# 02_MCU.net
KiCad netlist of a schematic drawn in Altium Designer
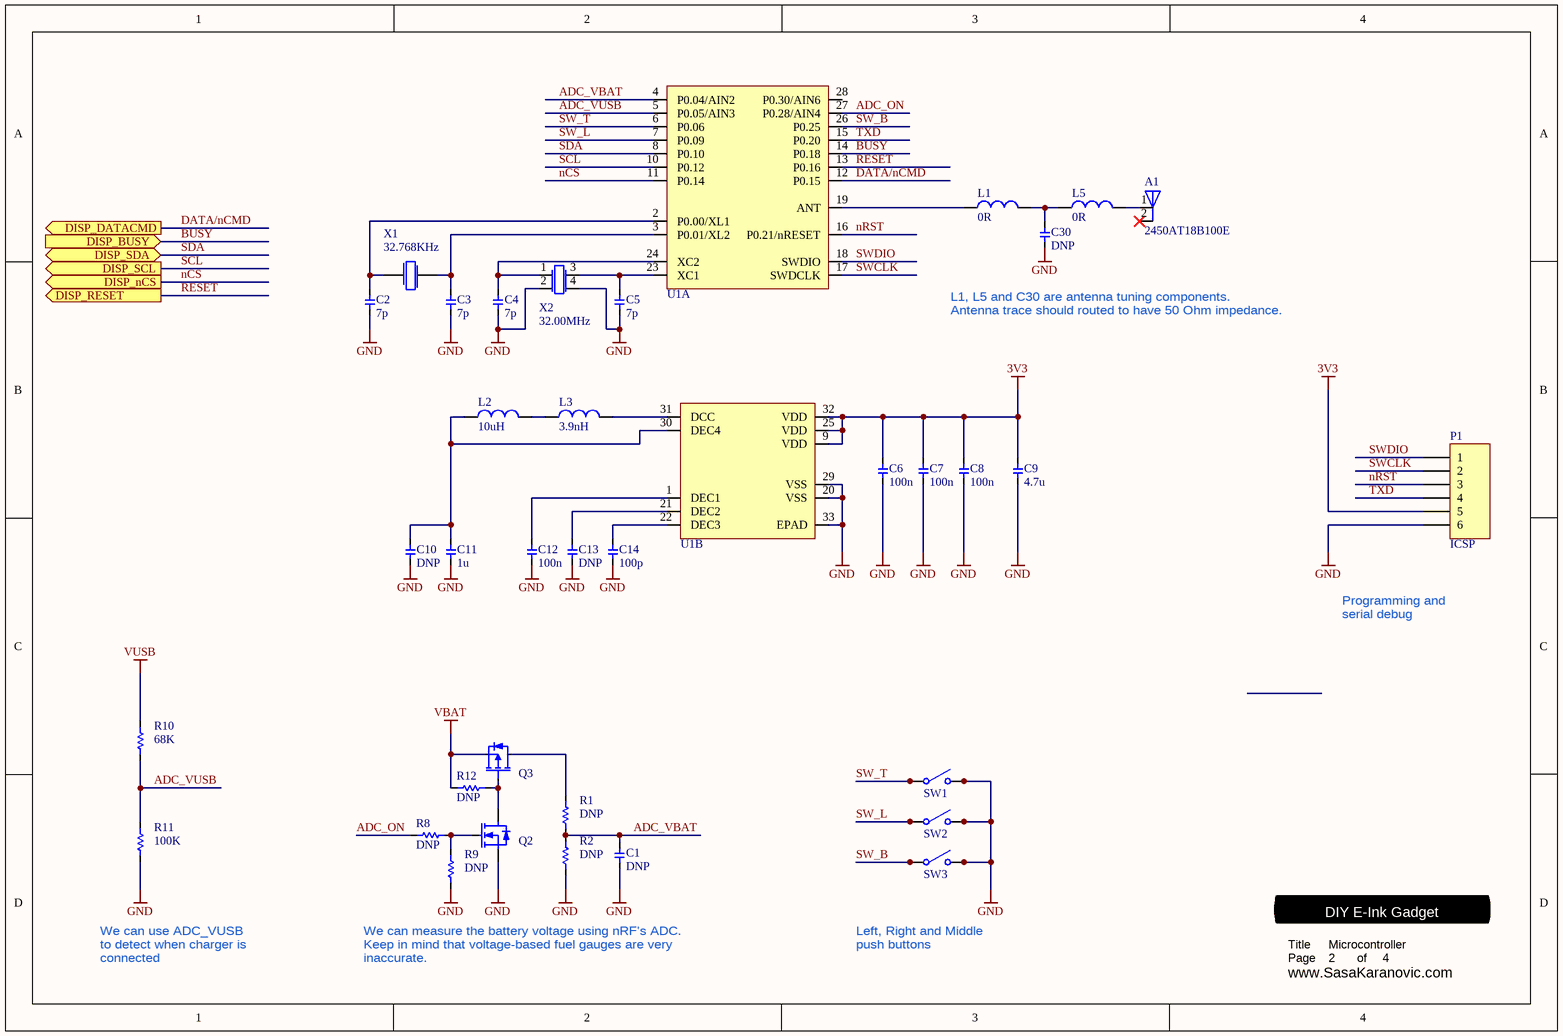
[diagram p0: 02_MCU.SchDoc]

(export (version "E")
  (design (tool "Eeschema 10.0.6"))
  (components
    (comp (ref "A1")
      (value "2450AT18B100E")
      (footprint "Footprint_Misc:2450AT18B100")
      (description "2.4GHz - Chip RF Antenna 2.4GHz ~ 2.5GHz 0.5dBi Solder Surface Mount")
      (fields
        (field (name "MANUFACTURER") "Johanson Technology Inc.")
        (field (name "DISTRIBUTOR PART NUMBER") "712-1006-1-ND")
      )
      (libsource (lib "Schematic_Misc") (part "2450AT18B100E"))
    )
    (comp (ref "C1")
      (value "DNP")
      (footprint "Footprint_Misc:0603 - CAP")
      (description "Capacitor")
      (fields (field (name "Comment") "Cap"))
      (libsource (lib "Schematic_Misc") (part "Cap"))
    )
    (comp (ref "C2")
      (value "7p")
      (footprint "Footprint_Misc:0603 - CAP")
      (description "Capacitor")
      (fields
        (field (name "MANUFACTURER") "Samsung Electro-Mechanics")
        (field (name "MANUFACTURER PART NUMBER") "CL10C070DB8NNNC")
      )
      (libsource (lib "Schematic_Misc") (part "Cap"))
    )
    (comp (ref "C3")
      (value "7p")
      (footprint "Footprint_Misc:0603 - CAP")
      (description "Capacitor")
      (fields
        (field (name "MANUFACTURER") "Samsung Electro-Mechanics")
        (field (name "MANUFACTURER PART NUMBER") "CL10C070DB8NNNC")
      )
      (libsource (lib "Schematic_Misc") (part "Cap"))
    )
    (comp (ref "C4")
      (value "7p")
      (footprint "Footprint_Misc:0603 - CAP")
      (description "Capacitor")
      (fields
        (field (name "MANUFACTURER") "Samsung Electro-Mechanics")
        (field (name "MANUFACTURER PART NUMBER") "CL10C070DB8NNNC")
      )
      (libsource (lib "Schematic_Misc") (part "Cap"))
    )
    (comp (ref "C5")
      (value "7p")
      (footprint "Footprint_Misc:0603 - CAP")
      (description "Capacitor")
      (fields
        (field (name "MANUFACTURER") "Samsung Electro-Mechanics")
        (field (name "MANUFACTURER PART NUMBER") "CL10C070DB8NNNC")
      )
      (libsource (lib "Schematic_Misc") (part "Cap"))
    )
    (comp (ref "C6")
      (value "100n")
      (footprint "Footprint_Misc:0603 - CAP")
      (description "Capacitor")
      (fields
        (field (name "MANUFACTURER") "Samsung Electro-Mechanics")
        (field (name "MANUFACTURER PART NUMBER") "CL10B104KB8NNWC")
      )
      (libsource (lib "Schematic_Misc") (part "Cap"))
    )
    (comp (ref "C7")
      (value "100n")
      (footprint "Footprint_Misc:0603 - CAP")
      (description "Capacitor")
      (fields
        (field (name "MANUFACTURER") "Samsung Electro-Mechanics")
        (field (name "MANUFACTURER PART NUMBER") "CL10B104KB8NNWC")
      )
      (libsource (lib "Schematic_Misc") (part "Cap"))
    )
    (comp (ref "C8")
      (value "100n")
      (footprint "Footprint_Misc:0603 - CAP")
      (description "Capacitor")
      (fields
        (field (name "MANUFACTURER") "Samsung Electro-Mechanics")
        (field (name "MANUFACTURER PART NUMBER") "CL10B104KB8NNWC")
      )
      (libsource (lib "Schematic_Misc") (part "Cap"))
    )
    (comp (ref "C9")
      (value "4.7u")
      (footprint "Footprint_Misc:0603 - CAP")
      (description "Capacitor")
      (fields
        (field (name "MANUFACTURER") "Samsung Electro-Mechanics")
        (field (name "MANUFACTURER PART NUMBER") "CL10B475KQ8NQNC")
      )
      (libsource (lib "Schematic_Misc") (part "Cap"))
    )
    (comp (ref "C10")
      (value "DNP")
      (footprint "Footprint_Misc:0603 - CAP")
      (description "Capacitor")
      (fields (field (name "Comment") "Cap"))
      (libsource (lib "Schematic_Misc") (part "Cap"))
    )
    (comp (ref "C11")
      (value "1u")
      (footprint "Footprint_Misc:0603 - CAP")
      (description "Capacitor")
      (fields
        (field (name "MANUFACTURER") "Samsung Electro-Mechanics")
        (field (name "MANUFACTURER PART NUMBER") "CL10B105KA8VPNC")
      )
      (libsource (lib "Schematic_Misc") (part "Cap"))
    )
    (comp (ref "C12")
      (value "100n")
      (footprint "Footprint_Misc:0603 - CAP")
      (description "Capacitor")
      (fields
        (field (name "MANUFACTURER") "Samsung Electro-Mechanics")
        (field (name "MANUFACTURER PART NUMBER") "CL10B104KB8NNWC")
      )
      (libsource (lib "Schematic_Misc") (part "Cap"))
    )
    (comp (ref "C13")
      (value "DNP")
      (footprint "Footprint_Misc:0603 - CAP")
      (description "Capacitor")
      (fields (field (name "Comment") "Cap"))
      (libsource (lib "Schematic_Misc") (part "Cap"))
    )
    (comp (ref "C14")
      (value "100p")
      (footprint "Footprint_Misc:0603 - CAP")
      (description "Capacitor")
      (fields
        (field (name "MANUFACTURER") "Samsung Electro-Mechanics")
        (field (name "MANUFACTURER PART NUMBER") "CL10C101JB8NNNC")
      )
      (libsource (lib "Schematic_Misc") (part "Cap"))
    )
    (comp (ref "C30")
      (value "DNP")
      (footprint "Footprint_Misc:0603 - CAP")
      (description "Capacitor")
      (fields (field (name "Comment") "Cap"))
      (libsource (lib "Schematic_Misc") (part "Cap"))
    )
    (comp (ref "L1")
      (value "0R")
      (footprint "Footprint_Misc:0603_IND")
      (description "Inductor")
      (fields
        (field (name "MANUFACTURER") "YAGEO")
        (field (name "MANUFACTURER PART NUMBER") "RC0603FR-070RL")
      )
      (libsource (lib "Schematic_Misc") (part "Inductor"))
    )
    (comp (ref "L2")
      (value "10uH")
      (footprint "Footprint_Misc:0603_IND")
      (description "Inductor")
      (fields
        (field (name "MANUFACTURER") "Abracon LLC")
        (field (name "MANUFACTURER PART NUMBER") "ASMCI-0603-100M-T")
      )
      (libsource (lib "Schematic_Misc") (part "Inductor"))
    )
    (comp (ref "L3")
      (value "3.9nH")
      (footprint "Footprint_Misc:0603_IND")
      (description "Inductor")
      (fields
        (field (name "MANUFACTURER") "Abracon LLC")
        (field (name "MANUFACTURER PART NUMBER") "AIMC-0603-3N9S-T")
      )
      (libsource (lib "Schematic_Misc") (part "Inductor"))
    )
    (comp (ref "L5")
      (value "0R")
      (footprint "Footprint_Misc:0603_IND")
      (description "Inductor")
      (fields
        (field (name "MANUFACTURER") "YAGEO")
        (field (name "MANUFACTURER PART NUMBER") "RC0603FR-070RL")
      )
      (libsource (lib "Schematic_Misc") (part "Inductor"))
    )
    (comp (ref "P1")
      (value "ICSP")
      (footprint "Footprint_Misc:Header 6x1 M - 90Deg - SMT")
      (description "Header, 6-Pin")
      (libsource (lib "Schematic_Misc") (part "Header 6"))
    )
    (comp (ref "Q2")
      (value "DMN62D0U-13")
      (footprint "Moji Footprintovi:SOT90P240X100-3N")
      (description "MOSFET N-CH 60V 0.38A")
      (fields
        (field (name "MANUFACTURER") "Diodes Incorporated")
        (field (name "DISTRIBUTOR PART NUMBER") "DMN62D0U-13DICT-ND")
      )
      (libsource (lib "Moji Schematici (1)") (part "DMN62D0U-13"))
    )
    (comp (ref "Q3")
      (value "DMP3017SFG")
      (footprint "Footprint_Misc:SOT-23")
      (description "P-Channel MOSFET")
      (libsource (lib "Schematic_Misc") (part "DMP3017SFG"))
    )
    (comp (ref "R1")
      (value "DNP")
      (footprint "Footprint_Misc:0603")
      (description "Resistor")
      (fields (field (name "Comment") "Res"))
      (libsource (lib "Schematic_Misc") (part "Res"))
    )
    (comp (ref "R2")
      (value "DNP")
      (footprint "Footprint_Misc:0603")
      (description "Resistor")
      (fields (field (name "Comment") "Res"))
      (libsource (lib "Schematic_Misc") (part "Res"))
    )
    (comp (ref "R8")
      (value "DNP")
      (footprint "Footprint_Misc:0603")
      (description "Resistor")
      (fields (field (name "Comment") "Res"))
      (libsource (lib "Schematic_Misc") (part "Res"))
    )
    (comp (ref "R9")
      (value "DNP")
      (footprint "Footprint_Misc:0603")
      (description "Resistor")
      (fields (field (name "Comment") "Res"))
      (libsource (lib "Schematic_Misc") (part "Res"))
    )
    (comp (ref "R10")
      (value "68K")
      (footprint "Footprint_Misc:0603")
      (description "Resistor")
      (fields
        (field (name "DISTRIBUTOR PART NUMBER") "311-68.0KHRCT-ND")
        (field (name "MANUFACTURER") "YAGEO")
      )
      (libsource (lib "Schematic_Misc") (part "Res"))
    )
    (comp (ref "R11")
      (value "100K")
      (footprint "Footprint_Misc:0603")
      (description "Resistor")
      (fields
        (field (name "DISTRIBUTOR PART NUMBER") "311-100KHRCT-ND")
        (field (name "MANUFACTURER") "YAGEO")
      )
      (libsource (lib "Schematic_Misc") (part "Res"))
    )
    (comp (ref "R12")
      (value "DNP")
      (footprint "Footprint_Misc:0603")
      (description "Resistor")
      (fields (field (name "Comment") "Res"))
      (libsource (lib "Schematic_Misc") (part "Res"))
    )
    (comp (ref "SW1")
      (value "SWITCH TACTILE SPST-NO 0.05A 12V")
      (footprint "Moji Footprintovi:PTS645")
      (fields
        (field (name "DISTRIBUTOR PART NUMBER") "CKN9088CT-ND")
        (field (name "MANUFACTURER") "C&K")
        (field (name "MANUFACTURER PART NUMBER") "PTS645SL50SMTR92 LFS")
      )
      (libsource (lib "Schematic_Misc") (part "PTS645SL50SMTR92 LFS"))
    )
    (comp (ref "SW2")
      (value "SWITCH TACTILE SPST-NO 0.05A 12V")
      (footprint "Moji Footprintovi:PTS645")
      (fields
        (field (name "DISTRIBUTOR PART NUMBER") "CKN9088CT-ND")
        (field (name "MANUFACTURER") "C&K")
        (field (name "MANUFACTURER PART NUMBER") "PTS645SL50SMTR92 LFS")
      )
      (libsource (lib "Schematic_Misc") (part "PTS645SL50SMTR92 LFS"))
    )
    (comp (ref "SW3")
      (value "SWITCH TACTILE SPST-NO 0.05A 12V")
      (footprint "Moji Footprintovi:PTS645")
      (fields
        (field (name "DISTRIBUTOR PART NUMBER") "CKN9088CT-ND")
        (field (name "MANUFACTURER") "C&K")
        (field (name "MANUFACTURER PART NUMBER") "PTS645SL50SMTR92 LFS")
      )
      (libsource (lib "Schematic_Misc") (part "PTS645SL50SMTR92 LFS"))
    )
    (comp (ref "U1")
      (value "NRF52810-QCAA-R")
      (footprint "Footprint_Misc:QFN50P500X500X100_HS-33N")
      (description "IC RF TxRx + MCU Bluetooth Bluetooth v5.0 2.4GHz 32-VFQFN Exposed Pad")
      (fields
        (field (name "MANUFACTURER") "Nordic Semiconductor ASA")
        (field (name "DISTRIBUTOR PART NUMBER") "1490-NRF52810-QCAA-RCT-ND")
      )
      (libsource (lib "Schematic_Misc") (part "NRF52810-QCAA-R"))
    )
    (comp (ref "X1")
      (value "32.768KHz")
      (footprint "Footprint_Misc:XTAL-2LEAD-3215")
      (description "32.768 kHz ±20ppm Crystal 7pF 70 kOhms 2-SMD, No Lead")
      (fields
        (field (name "MANUFACTURER") "ECS Inc.")
        (field (name "MANUFACTURER PART NUMBER") "ECS-320-8-37B-CKY-TR")
      )
      (libsource (lib "Schematic_Misc") (part "XTAL-32.768KHz-SC32S-7PF20PPM"))
    )
    (comp (ref "X2")
      (value "32.00MHz")
      (footprint "Footprint_Misc:XTAL-4LEAD-2016")
      (description "32 MHz ±10ppm Crystal 8pF 50 Ohms 4-SMD, No Lead")
      (fields
        (field (name "MANUFACTURER") "ECS Inc.")
        (field (name "MANUFACTURER PART NUMBER") "ECS-320-8-37B-CKY-TR")
      )
      (libsource (lib "Schematic_Misc") (part "XTAL-32MHz-ECS-320-8-37B-CKY-TR"))
    )
  )
  (nets
    (net (code "1") (name "/ADC_ON") (class "Default")
      (node (ref "R8") (pin "2") (pinfunction "2_2") (pintype "passive"))
      (node (ref "U1") (pin "27") (pinfunction "_P0.28/AIN4_27") (pintype "passive"))
    )
    (net (code "2") (name "/ADC_VBAT") (class "Default")
      (node (ref "C1") (pin "2") (pinfunction "2_2") (pintype "passive"))
      (node (ref "R1") (pin "1") (pinfunction "1_1") (pintype "passive"))
      (node (ref "R2") (pin "2") (pinfunction "2_2") (pintype "passive"))
      (node (ref "U1") (pin "4") (pinfunction "_P0.04/AIN2_4") (pintype "passive"))
    )
    (net (code "3") (name "/ADC_VUSB") (class "Default")
      (node (ref "R10") (pin "1") (pinfunction "1_1") (pintype "passive"))
      (node (ref "R11") (pin "2") (pinfunction "2_2") (pintype "passive"))
      (node (ref "U1") (pin "5") (pinfunction "_P0.05/AIN3_5") (pintype "passive"))
    )
    (net (code "4") (name "/BUSY") (class "Default")
      (node (ref "U1") (pin "14") (pinfunction "_P0.18_14") (pintype "passive"))
    )
    (net (code "5") (name "/DATA{slash}nCMD") (class "Default")
      (node (ref "U1") (pin "12") (pinfunction "_P0.15_12") (pintype "passive"))
    )
    (net (code "6") (name "/RESET") (class "Default")
      (node (ref "U1") (pin "13") (pinfunction "_P0.16_13") (pintype "passive"))
    )
    (net (code "7") (name "/SCL") (class "Default")
      (node (ref "U1") (pin "10") (pinfunction "_P0.12_10") (pintype "passive"))
    )
    (net (code "8") (name "/SDA") (class "Default")
      (node (ref "U1") (pin "8") (pinfunction "_P0.10_8") (pintype "passive"))
    )
    (net (code "9") (name "/SWCLK") (class "Default")
      (node (ref "P1") (pin "2") (pinfunction "2_2") (pintype "passive"))
      (node (ref "U1") (pin "17") (pinfunction "_SWDCLK_17") (pintype "passive"))
    )
    (net (code "10") (name "/SWDIO") (class "Default")
      (node (ref "P1") (pin "1") (pinfunction "1_1") (pintype "passive"))
      (node (ref "U1") (pin "18") (pinfunction "_SWDIO_18") (pintype "passive"))
    )
    (net (code "11") (name "/SW_B") (class "Default")
      (node (ref "SW3") (pin "1") (pinfunction "COMMON1_1") (pintype "passive"))
      (node (ref "SW3") (pin "2") (pinfunction "COMMON1_2") (pintype "passive"))
      (node (ref "U1") (pin "26") (pinfunction "_P0.25_26") (pintype "passive"))
    )
    (net (code "12") (name "/SW_L") (class "Default")
      (node (ref "SW2") (pin "1") (pinfunction "COMMON1_1") (pintype "passive"))
      (node (ref "SW2") (pin "2") (pinfunction "COMMON1_2") (pintype "passive"))
      (node (ref "U1") (pin "7") (pinfunction "_P0.09_7") (pintype "passive"))
    )
    (net (code "13") (name "/SW_T") (class "Default")
      (node (ref "SW1") (pin "1") (pinfunction "COMMON1_1") (pintype "passive"))
      (node (ref "SW1") (pin "2") (pinfunction "COMMON1_2") (pintype "passive"))
      (node (ref "U1") (pin "6") (pinfunction "_P0.06_6") (pintype "passive"))
    )
    (net (code "14") (name "/TXD") (class "Default")
      (node (ref "P1") (pin "4") (pinfunction "4_4") (pintype "passive"))
      (node (ref "U1") (pin "15") (pinfunction "_P0.20_15") (pintype "passive"))
    )
    (net (code "15") (name "/nCS") (class "Default")
      (node (ref "U1") (pin "11") (pinfunction "_P0.14_11") (pintype "passive"))
    )
    (net (code "16") (name "/nRST") (class "Default")
      (node (ref "P1") (pin "3") (pinfunction "3_3") (pintype "passive"))
      (node (ref "U1") (pin "16") (pinfunction "_P0.21/nRESET_16") (pintype "passive"))
    )
    (net (code "17") (name "3V3") (class "Default")
      (node (ref "C6") (pin "2") (pinfunction "2_2") (pintype "passive"))
      (node (ref "C7") (pin "2") (pinfunction "2_2") (pintype "passive"))
      (node (ref "C8") (pin "2") (pinfunction "2_2") (pintype "passive"))
      (node (ref "C9") (pin "2") (pinfunction "2_2") (pintype "passive"))
      (node (ref "P1") (pin "5") (pinfunction "5_5") (pintype "passive"))
      (node (ref "U1") (pin "25") (pinfunction "_VDD_25") (pintype "passive"))
      (node (ref "U1") (pin "32") (pinfunction "_VDD_32") (pintype "passive"))
      (node (ref "U1") (pin "9") (pinfunction "_VDD_9") (pintype "passive"))
    )
    (net (code "18") (name "GND") (class "Default")
      (node (ref "C1") (pin "1") (pinfunction "1_1") (pintype "passive"))
      (node (ref "C10") (pin "1") (pinfunction "1_1") (pintype "passive"))
      (node (ref "C11") (pin "1") (pinfunction "1_1") (pintype "passive"))
      (node (ref "C12") (pin "1") (pinfunction "1_1") (pintype "passive"))
      (node (ref "C13") (pin "1") (pinfunction "1_1") (pintype "passive"))
      (node (ref "C14") (pin "1") (pinfunction "1_1") (pintype "passive"))
      (node (ref "C2") (pin "1") (pinfunction "1_1") (pintype "passive"))
      (node (ref "C3") (pin "1") (pinfunction "1_1") (pintype "passive"))
      (node (ref "C30") (pin "1") (pinfunction "1_1") (pintype "passive"))
      (node (ref "C4") (pin "1") (pinfunction "1_1") (pintype "passive"))
      (node (ref "C5") (pin "1") (pinfunction "1_1") (pintype "passive"))
      (node (ref "C6") (pin "1") (pinfunction "1_1") (pintype "passive"))
      (node (ref "C7") (pin "1") (pinfunction "1_1") (pintype "passive"))
      (node (ref "C8") (pin "1") (pinfunction "1_1") (pintype "passive"))
      (node (ref "C9") (pin "1") (pinfunction "1_1") (pintype "passive"))
      (node (ref "P1") (pin "6") (pinfunction "6_6") (pintype "passive"))
      (node (ref "Q2") (pin "2") (pinfunction "S_2") (pintype "passive"))
      (node (ref "R11") (pin "1") (pinfunction "1_1") (pintype "passive"))
      (node (ref "R2") (pin "1") (pinfunction "1_1") (pintype "passive"))
      (node (ref "R9") (pin "1") (pinfunction "1_1") (pintype "passive"))
      (node (ref "SW1") (pin "3") (pinfunction "COMMON2_3") (pintype "passive"))
      (node (ref "SW1") (pin "4") (pinfunction "COMMON2_4") (pintype "passive"))
      (node (ref "SW2") (pin "3") (pinfunction "COMMON2_3") (pintype "passive"))
      (node (ref "SW2") (pin "4") (pinfunction "COMMON2_4") (pintype "passive"))
      (node (ref "SW3") (pin "3") (pinfunction "COMMON2_3") (pintype "passive"))
      (node (ref "SW3") (pin "4") (pinfunction "COMMON2_4") (pintype "passive"))
      (node (ref "U1") (pin "20") (pinfunction "_VSS_20") (pintype "passive"))
      (node (ref "U1") (pin "29") (pinfunction "_VSS_29") (pintype "passive"))
      (node (ref "U1") (pin "33") (pinfunction "EPAD_33") (pintype "passive"))
      (node (ref "X2") (pin "2") (pinfunction "GND_2") (pintype "passive"))
      (node (ref "X2") (pin "4") (pinfunction "GND_4") (pintype "passive"))
    )
    (net (code "19") (name "Net-(A1-FEED)") (class "Default")
      (node (ref "A1") (pin "1") (pinfunction "FEED_1") (pintype "passive"))
      (node (ref "L5") (pin "2") (pinfunction "2_2") (pintype "passive"))
    )
    (net (code "20") (name "Net-(C30-Pad2)") (class "Default")
      (node (ref "C30") (pin "2") (pinfunction "2_2") (pintype "passive"))
      (node (ref "L1") (pin "2") (pinfunction "2_2") (pintype "passive"))
      (node (ref "L5") (pin "1") (pinfunction "1_1") (pintype "passive"))
    )
    (net (code "21") (name "Net-(L2-Pad2)") (class "Default")
      (node (ref "L2") (pin "2") (pinfunction "2_2") (pintype "passive"))
      (node (ref "L3") (pin "1") (pinfunction "1_1") (pintype "passive"))
    )
    (net (code "22") (name "Net-(Q2-D)") (class "Default")
      (node (ref "Q2") (pin "3") (pinfunction "D_3") (pintype "passive"))
      (node (ref "Q3") (pin "1") (pinfunction "G_1") (pintype "passive"))
      (node (ref "R12") (pin "1") (pinfunction "1_1") (pintype "passive"))
    )
    (net (code "23") (name "Net-(Q2-G)") (class "Default")
      (node (ref "Q2") (pin "1") (pinfunction "G_1") (pintype "passive"))
      (node (ref "R8") (pin "1") (pinfunction "1_1") (pintype "passive"))
      (node (ref "R9") (pin "2") (pinfunction "2_2") (pintype "passive"))
    )
    (net (code "24") (name "Net-(Q3-D)") (class "Default")
      (node (ref "Q3") (pin "2") (pinfunction "D_2") (pintype "passive"))
      (node (ref "R1") (pin "2") (pinfunction "2_2") (pintype "passive"))
    )
    (net (code "25") (name "Net-(U1A-_ANT)") (class "Default")
      (node (ref "L1") (pin "1") (pinfunction "1_1") (pintype "passive"))
      (node (ref "U1") (pin "19") (pinfunction "_ANT_19") (pintype "passive"))
    )
    (net (code "26") (name "Net-(U1A-_P0.00{slash}XL1)") (class "Default")
      (node (ref "C2") (pin "2") (pinfunction "2_2") (pintype "passive"))
      (node (ref "U1") (pin "2") (pinfunction "_P0.00/XL1_2") (pintype "passive"))
      (node (ref "X1") (pin "1") (pintype "passive"))
    )
    (net (code "27") (name "Net-(U1A-_P0.01{slash}XL2)") (class "Default")
      (node (ref "C3") (pin "2") (pinfunction "2_2") (pintype "passive"))
      (node (ref "U1") (pin "3") (pinfunction "_P0.01/XL2_3") (pintype "passive"))
      (node (ref "X1") (pin "2") (pintype "passive"))
    )
    (net (code "28") (name "Net-(U1A-_XC1)") (class "Default")
      (node (ref "C5") (pin "2") (pinfunction "2_2") (pintype "passive"))
      (node (ref "U1") (pin "23") (pinfunction "_XC1_23") (pintype "passive"))
      (node (ref "X2") (pin "3") (pinfunction "OSC3_3") (pintype "passive"))
    )
    (net (code "29") (name "Net-(U1A-_XC2)") (class "Default")
      (node (ref "C4") (pin "2") (pinfunction "2_2") (pintype "passive"))
      (node (ref "U1") (pin "24") (pinfunction "_XC2_24") (pintype "passive"))
      (node (ref "X2") (pin "1") (pinfunction "OSC1_1") (pintype "passive"))
    )
    (net (code "30") (name "Net-(U1B-_DCC)") (class "Default")
      (node (ref "L3") (pin "2") (pinfunction "2_2") (pintype "passive"))
      (node (ref "U1") (pin "31") (pinfunction "_DCC_31") (pintype "passive"))
    )
    (net (code "31") (name "Net-(U1B-_DEC1)") (class "Default")
      (node (ref "C12") (pin "2") (pinfunction "2_2") (pintype "passive"))
      (node (ref "U1") (pin "1") (pinfunction "_DEC1_1") (pintype "passive"))
    )
    (net (code "32") (name "Net-(U1B-_DEC2)") (class "Default")
      (node (ref "C13") (pin "2") (pinfunction "2_2") (pintype "passive"))
      (node (ref "U1") (pin "21") (pinfunction "_DEC2_21") (pintype "passive"))
    )
    (net (code "33") (name "Net-(U1B-_DEC3)") (class "Default")
      (node (ref "C14") (pin "2") (pinfunction "2_2") (pintype "passive"))
      (node (ref "U1") (pin "22") (pinfunction "_DEC3_22") (pintype "passive"))
    )
    (net (code "34") (name "Net-(U1B-_DEC4)") (class "Default")
      (node (ref "C10") (pin "2") (pinfunction "2_2") (pintype "passive"))
      (node (ref "C11") (pin "2") (pinfunction "2_2") (pintype "passive"))
      (node (ref "L2") (pin "1") (pinfunction "1_1") (pintype "passive"))
      (node (ref "U1") (pin "30") (pinfunction "_DEC4_30") (pintype "passive"))
    )
    (net (code "35") (name "VBAT") (class "Default")
      (node (ref "Q3") (pin "3") (pinfunction "S_3") (pintype "passive"))
      (node (ref "R12") (pin "2") (pinfunction "2_2") (pintype "passive"))
    )
    (net (code "36") (name "VUSB") (class "Default")
      (node (ref "R10") (pin "2") (pinfunction "2_2") (pintype "passive"))
    )
    (net (code "37") (name "unconnected-(A1-NC-Pad2)") (class "Default")
      (node (ref "A1") (pin "2") (pinfunction "NC_2") (pintype "passive+no_connect"))
    )
    (net (code "38") (name "unconnected-(U1A-_P0.30{slash}AIN6-Pad28)") (class "Default")
      (node (ref "U1") (pin "28") (pinfunction "_P0.30/AIN6_28") (pintype "passive"))
    )
  )
)
